# DM2097_EEPROM.net
KiCad netlist of a schematic drawn in Altium Designer
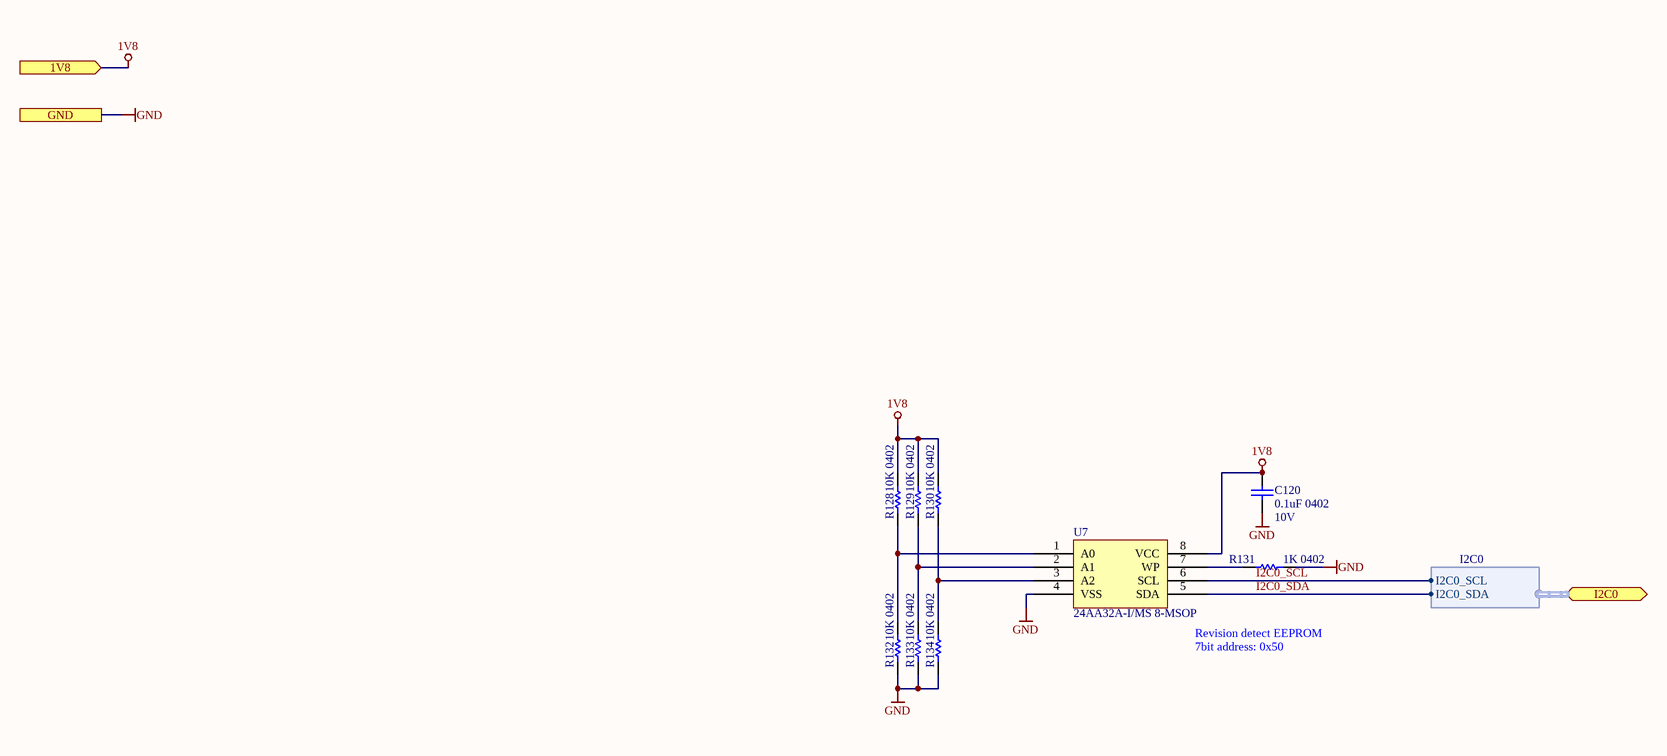
[diagram p0: DM2097_EEPROM.SchDoc]

(export (version "E")
  (design (tool "Eeschema 10.0.6"))
  (components
    (comp (ref "C120")
      (value "0.1uF 0402")
      (footprint "CAP_Altium_Vault_Generic:CAPC0402(1005)70_L")
      (description "CAP CER 0.1UF 10V X7R 0402 5%")
      (fields (field (name "TOLERANCE") "5%") (field (name "VOLTAGE RATING") "10V"))
      (libsource (lib "LuxonisMaster") (part "GRM155R71A104JA01D"))
    )
    (comp (ref "R128")
      (value "10K 0402")
      (footprint "RES_Altium_Vault_Generic:RESC0402(1005)_L")
      (fields (field (name "TOLERANCE") "1%"))
      (libsource (lib "LuxonisMaster") (part "RC0402FR-1310KL"))
    )
    (comp (ref "R129")
      (value "10K 0402")
      (footprint "RES_Altium_Vault_Generic:RESC0402(1005)_L")
      (fields (field (name "TOLERANCE") "1%"))
      (libsource (lib "LuxonisMaster") (part "RC0402FR-1310KL"))
    )
    (comp (ref "R130")
      (value "10K 0402")
      (footprint "RES_Altium_Vault_Generic:RESC0402(1005)_L")
      (fields (field (name "TOLERANCE") "1%"))
      (libsource (lib "LuxonisMaster") (part "RC0402FR-1310KL"))
    )
    (comp (ref "R131")
      (value "1K 0402")
      (footprint "RES_Altium_Vault_Generic:RESC0402(1005)_L")
      (description "RES SMD 1K OHM 1% 1/16W 0402")
      (fields (field (name "TOLERANCE") "1%"))
      (libsource (lib "LuxonisMaster") (part "RC0402FR-071KL"))
    )
    (comp (ref "R132")
      (value "10K 0402")
      (footprint "RES_Altium_Vault_Generic:RESC0402(1005)_L")
      (fields (field (name "TOLERANCE") "1%"))
      (libsource (lib "LuxonisMaster") (part "RC0402FR-1310KL"))
    )
    (comp (ref "R133")
      (value "10K 0402")
      (footprint "RES_Altium_Vault_Generic:RESC0402(1005)_L")
      (fields (field (name "TOLERANCE") "1%"))
      (libsource (lib "LuxonisMaster") (part "RC0402FR-1310KL"))
    )
    (comp (ref "R134")
      (value "10K 0402")
      (footprint "RES_Altium_Vault_Generic:RESC0402(1005)_L")
      (fields (field (name "TOLERANCE") "1%"))
      (libsource (lib "LuxonisMaster") (part "RC0402FR-1310KL"))
    )
    (comp (ref "U7")
      (value "24AA32A-I/MS 8-MSOP")
      (footprint "LuxonisMaster:24AA32A-I/MS")
      (description "IC EEPROM 32K I2C 400KHZ 8MSOP Memory IC 32Kb (4K x 8) I²C 400kHz 900ns 8-MSOP")
      (libsource (lib "LuxonisMaster") (part "24AA32A-I/MS"))
    )
  )
  (nets
    (net (code "2") (name "/I2C0_SCL") (class "Default")
      (node (ref "U7") (pin "6") (pinfunction "SCL_6") (pintype "passive"))
    )
    (net (code "3") (name "/I2C0_SDA") (class "Default")
      (node (ref "U7") (pin "5") (pinfunction "SDA_5") (pintype "passive"))
    )
    (net (code "5") (name "1V8") (class "Default")
      (node (ref "C120") (pin "2") (pinfunction "2_2") (pintype "passive"))
      (node (ref "R128") (pin "2") (pinfunction "2_2") (pintype "passive"))
      (node (ref "R129") (pin "2") (pinfunction "2_2") (pintype "passive"))
      (node (ref "R130") (pin "2") (pinfunction "2_2") (pintype "passive"))
      (node (ref "U7") (pin "8") (pinfunction "VCC_8") (pintype "passive"))
    )
    (net (code "6") (name "GND") (class "Default")
      (node (ref "C120") (pin "1") (pinfunction "1_1") (pintype "passive"))
      (node (ref "R131") (pin "1") (pinfunction "1_1") (pintype "passive"))
      (node (ref "R132") (pin "1") (pinfunction "1_1") (pintype "passive"))
      (node (ref "R133") (pin "1") (pinfunction "1_1") (pintype "passive"))
      (node (ref "R134") (pin "1") (pinfunction "1_1") (pintype "passive"))
      (node (ref "U7") (pin "4") (pinfunction "VSS_4") (pintype "passive"))
    )
    (net (code "7") (name "Net-(U7-A0)") (class "Default")
      (node (ref "R128") (pin "1") (pinfunction "1_1") (pintype "passive"))
      (node (ref "R132") (pin "2") (pinfunction "2_2") (pintype "passive"))
      (node (ref "U7") (pin "1") (pinfunction "A0_1") (pintype "passive"))
    )
    (net (code "8") (name "Net-(U7-A1)") (class "Default")
      (node (ref "R129") (pin "1") (pinfunction "1_1") (pintype "passive"))
      (node (ref "R133") (pin "2") (pinfunction "2_2") (pintype "passive"))
      (node (ref "U7") (pin "2") (pinfunction "A1_2") (pintype "passive"))
    )
    (net (code "9") (name "Net-(U7-A2)") (class "Default")
      (node (ref "R130") (pin "1") (pinfunction "1_1") (pintype "passive"))
      (node (ref "R134") (pin "2") (pinfunction "2_2") (pintype "passive"))
      (node (ref "U7") (pin "3") (pinfunction "A2_3") (pintype "passive"))
    )
    (net (code "10") (name "Net-(U7-WP)") (class "Default")
      (node (ref "R131") (pin "2") (pinfunction "2_2") (pintype "passive"))
      (node (ref "U7") (pin "7") (pinfunction "WP_7") (pintype "passive"))
    )
  )
)
